# ESPTempLogger.net
KiCad netlist of a schematic drawn in EAGLE
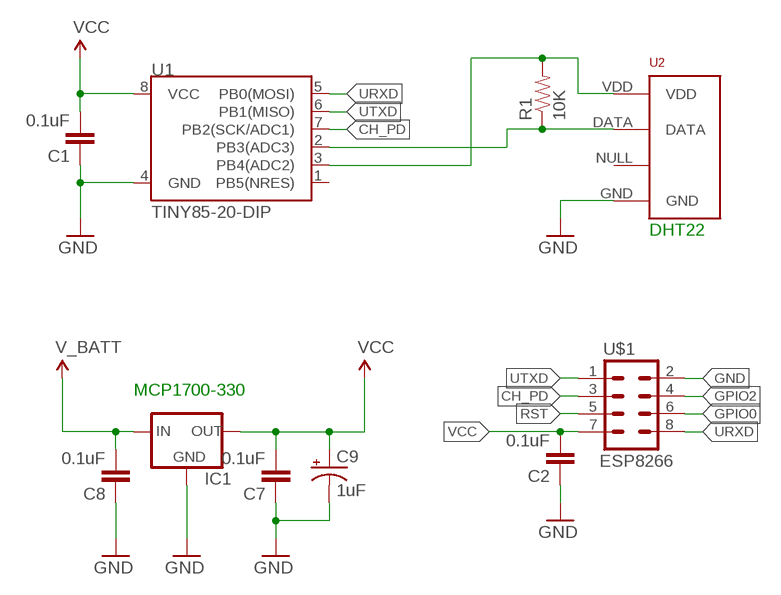
[diagram p0: schematic, sheet 1]

(export (version "E")
  (design (tool "Eeschema 10.0.6"))
  (components
    (comp (ref "C1")
      (value "0.1uF")
      (footprint "eagle-import:CAP-PTH-SMALL")
      (libsource (lib "eagle-import") (part "CAPPTH"))
    )
    (comp (ref "C2")
      (value "0.1uF")
      (footprint "eagle-import:CAP-PTH-SMALL")
      (libsource (lib "eagle-import") (part "CAPPTH"))
    )
    (comp (ref "C7")
      (value "0.1uF")
      (footprint "eagle-import:CAP-PTH-SMALL")
      (libsource (lib "eagle-import") (part "CAPPTH"))
    )
    (comp (ref "C8")
      (value "0.1uF")
      (footprint "eagle-import:CAP-PTH-SMALL")
      (libsource (lib "eagle-import") (part "CAPPTH"))
    )
    (comp (ref "C9")
      (value "1uF")
      (footprint "eagle-import:CPOL-RADIAL-10UF-25V")
      (libsource (lib "eagle-import") (part "CAP_POLPTH2"))
    )
    (comp (ref "IC1")
      (value "V_REG_78XXTO-92_UNTESTED")
      (footprint "eagle-import:TO-92")
      (libsource (lib "eagle-import") (part "V_REG_78XXTO-92_UNTESTED"))
    )
    (comp (ref "R1")
      (value "10K")
      (footprint "eagle-import:AXIAL-0.4")
      (libsource (lib "eagle-import") (part "RESISTORPTH-1/4W"))
    )
    (comp (ref "U$1")
      (value "ESP8266")
      (footprint "eagle-import:2X4")
      (libsource (lib "eagle-import") (part "M04X2"))
    )
    (comp (ref "U1")
      (value "TINY85-20-DIP")
      (footprint "eagle-import:DIP08")
      (libsource (lib "eagle-import") (part "ATTINY45TINY85-20-DIP"))
    )
    (comp (ref "U2")
      (value "RHT03_DHT-22_AM2302RA")
      (footprint "eagle-import:RHT03_DHT-22_RA")
      (libsource (lib "eagle-import") (part "RHT03_DHT-22_AM2302RA"))
    )
  )
  (nets
    (net (code "1") (name "CH_PD") (class "Default")
      (node (ref "U$1") (pin "3") (pinfunction "3_3") (pintype "passive"))
      (node (ref "U1") (pin "7") (pinfunction "PB2(SCK/ADC1)_7") (pintype "bidirectional"))
    )
    (net (code "2") (name "GND") (class "Default")
      (node (ref "C1") (pin "1") (pinfunction "1_1") (pintype "passive"))
      (node (ref "C2") (pin "1") (pinfunction "1_1") (pintype "passive"))
      (node (ref "C7") (pin "1") (pinfunction "1_1") (pintype "passive"))
      (node (ref "C8") (pin "1") (pinfunction "1_1") (pintype "passive"))
      (node (ref "C9") (pin "2") (pinfunction "-_2") (pintype "passive"))
      (node (ref "IC1") (pin "1") (pinfunction "GND_1") (pintype "input"))
      (node (ref "U$1") (pin "2") (pinfunction "2_2") (pintype "passive"))
      (node (ref "U1") (pin "4") (pinfunction "GND_4") (pintype "bidirectional"))
      (node (ref "U2") (pin "GND") (pinfunction "GND_GND") (pintype "power_in"))
    )
    (net (code "3") (name "GPIO0") (class "Default")
      (node (ref "U$1") (pin "6") (pinfunction "6_6") (pintype "passive"))
    )
    (net (code "4") (name "GPIO2") (class "Default")
      (node (ref "U$1") (pin "4") (pinfunction "4_4") (pintype "passive"))
    )
    (net (code "5") (name "Net-(R1-1)") (class "Default")
      (node (ref "R1") (pin "P$1") (pinfunction "1_P$1") (pintype "passive"))
      (node (ref "U1") (pin "2") (pinfunction "PB3(ADC3)_2") (pintype "bidirectional"))
      (node (ref "U2") (pin "DATA") (pinfunction "DATA_DATA") (pintype "bidirectional"))
    )
    (net (code "6") (name "Net-(R1-2)") (class "Default")
      (node (ref "R1") (pin "P$2") (pinfunction "2_P$2") (pintype "passive"))
      (node (ref "U1") (pin "3") (pinfunction "PB4(ADC2)_3") (pintype "bidirectional"))
      (node (ref "U2") (pin "VDD") (pinfunction "VDD_VDD") (pintype "power_in"))
    )
    (net (code "7") (name "RST") (class "Default")
      (node (ref "U$1") (pin "5") (pinfunction "5_5") (pintype "passive"))
    )
    (net (code "8") (name "URXD") (class "Default")
      (node (ref "U$1") (pin "8") (pinfunction "8_8") (pintype "passive"))
      (node (ref "U1") (pin "5") (pinfunction "PB0(MOSI)_5") (pintype "bidirectional"))
    )
    (net (code "9") (name "UTXD") (class "Default")
      (node (ref "U$1") (pin "1") (pinfunction "1_1") (pintype "passive"))
      (node (ref "U1") (pin "6") (pinfunction "PB1(MISO)_6") (pintype "bidirectional"))
    )
    (net (code "10") (name "VCC") (class "Default")
      (node (ref "C1") (pin "2") (pinfunction "2_2") (pintype "passive"))
      (node (ref "C2") (pin "2") (pinfunction "2_2") (pintype "passive"))
      (node (ref "C7") (pin "2") (pinfunction "2_2") (pintype "passive"))
      (node (ref "C9") (pin "1") (pinfunction "+_1") (pintype "passive"))
      (node (ref "IC1") (pin "3") (pinfunction "OUT_3") (pintype "output"))
      (node (ref "U$1") (pin "7") (pinfunction "7_7") (pintype "passive"))
      (node (ref "U1") (pin "8") (pinfunction "VCC_8") (pintype "bidirectional"))
    )
    (net (code "11") (name "V_BATT") (class "Default")
      (node (ref "C8") (pin "2") (pinfunction "2_2") (pintype "passive"))
      (node (ref "IC1") (pin "2") (pinfunction "IN_2") (pintype "input"))
    )
    (net (code "12") (name "unconnected-(U1-PB5(NRES)-Pad1)") (class "Default")
      (node (ref "U1") (pin "1") (pinfunction "PB5(NRES)_1") (pintype "bidirectional"))
    )
    (net (code "13") (name "unconnected-(U2-PadNULL)") (class "Default")
      (node (ref "U2") (pin "NULL") (pinfunction "NULL_NULL") (pintype "no_connect"))
    )
  )
)
